# LR_meter.net
KiCad netlist of a schematic drawn in EAGLE
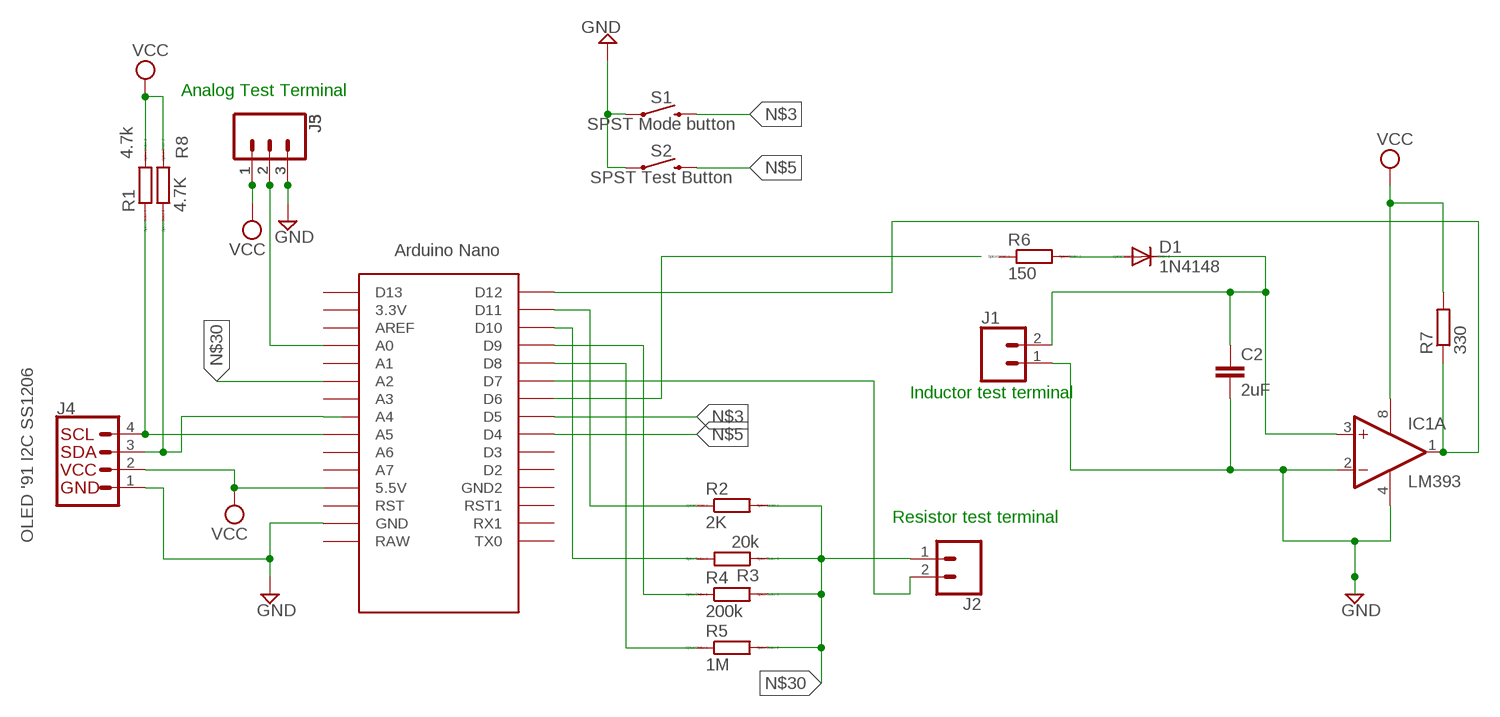
[diagram p0: schematic, sheet 1]

(export (version "E")
  (design (tool "Eeschema 10.0.6"))
  (components
    (comp (ref "C2")
      (value "2uF")
      (footprint "eagle-import:C5B2.5")
      (libsource (lib "eagle-import") (part "C5/2.5"))
    )
    (comp (ref "D1")
      (value "1N4148")
      (footprint "eagle-import:DO35-10")
      (libsource (lib "eagle-import") (part "1N4148DO35-10"))
    )
    (comp (ref "IC1")
      (value "LM393")
      (footprint "eagle-import:DIL08")
      (libsource (lib "eagle-import") (part "LM393N"))
    )
    (comp (ref "J1")
      (value "CONN_02")
      (footprint "eagle-import:1X02")
      (libsource (lib "eagle-import") (part "CONN_02"))
    )
    (comp (ref "J2")
      (value "CONN_02")
      (footprint "eagle-import:1X02")
      (libsource (lib "eagle-import") (part "CONN_02"))
    )
    (comp (ref "J3")
      (value "CONN_031X03_SMD_RA_MALE_POST_SMALLEST")
      (footprint "eagle-import:1X03_SMD_RA_MALE_POST_SMALLEST")
      (libsource (lib "eagle-import") (part "CONN_031X03_SMD_RA_MALE_POST_SMALLEST"))
    )
    (comp (ref "J4")
      (value "OLED '91 I2C SS1206")
      (footprint "eagle-import:1X04")
      (libsource (lib "eagle-import") (part "I2C_STANDARD"))
    )
    (comp (ref "J5")
      (value "CONN_031X03_SMD_RA_MALE_POST_SMALLEST")
      (footprint "eagle-import:1X03_SMD_RA_MALE_POST_SMALLEST")
      (libsource (lib "eagle-import") (part "CONN_031X03_SMD_RA_MALE_POST_SMALLEST"))
    )
    (comp (ref "R1")
      (value "4.7k")
      (footprint "eagle-import:0207_10")
      (libsource (lib "eagle-import") (part "R0207/10"))
    )
    (comp (ref "R2")
      (value "2K")
      (footprint "eagle-import:0207_10")
      (libsource (lib "eagle-import") (part "R0207/10"))
    )
    (comp (ref "R3")
      (value "20k")
      (footprint "eagle-import:0207_10")
      (libsource (lib "eagle-import") (part "R0207/10"))
    )
    (comp (ref "R4")
      (value "200k")
      (footprint "eagle-import:0207_10")
      (libsource (lib "eagle-import") (part "R0207/10"))
    )
    (comp (ref "R5")
      (value "1M")
      (footprint "eagle-import:0207_10")
      (libsource (lib "eagle-import") (part "R0207/10"))
    )
    (comp (ref "R6")
      (value "150")
      (footprint "eagle-import:0207_10")
      (libsource (lib "eagle-import") (part "R0207/10"))
    )
    (comp (ref "R7")
      (value "330")
      (footprint "eagle-import:0207_15")
      (libsource (lib "eagle-import") (part "R-EU_0207/15"))
    )
    (comp (ref "R8")
      (value "4.7K")
      (footprint "eagle-import:0207_10")
      (libsource (lib "eagle-import") (part "R0207/10"))
    )
    (comp (ref "S1")
      (value "SPST Mode button")
      (footprint "eagle-import:TACTILE_SWITCH_PTH_6.0MM_KIT")
      (libsource (lib "eagle-import") (part "MOMENTARY-SWITCH-SPST-PTH-6.0MM-KIT"))
    )
    (comp (ref "S2")
      (value "SPST Test Button")
      (footprint "eagle-import:TACTILE_SWITCH_PTH_6.0MM_KIT")
      (libsource (lib "eagle-import") (part "MOMENTARY-SWITCH-SPST-PTH-6.0MM-KIT"))
    )
    (comp (ref "U$1")
      (value "NANO")
      (footprint "eagle-import:NANO")
      (libsource (lib "eagle-import") (part "NANO"))
    )
  )
  (nets
    (net (code "1") (name "GND") (class "Default")
      (node (ref "C2") (pin "2") (pinfunction "2_2") (pintype "passive"))
      (node (ref "IC1") (pin "2") (pinfunction "-IN_2") (pintype "input"))
      (node (ref "IC1") (pin "4") (pinfunction "V-_4") (pintype "power_in"))
      (node (ref "J1") (pin "1") (pinfunction "1_1") (pintype "passive"))
      (node (ref "J3") (pin "3") (pinfunction "3_3") (pintype "passive"))
      (node (ref "J4") (pin "1") (pinfunction "1_1") (pintype "power_in"))
      (node (ref "J5") (pin "3") (pinfunction "3_3") (pintype "passive"))
      (node (ref "S1") (pin "1") (pinfunction "1_1") (pintype "passive"))
      (node (ref "S2") (pin "1") (pinfunction "1_1") (pintype "passive"))
      (node (ref "U$1") (pin "GND") (pinfunction "GND_GND") (pintype "bidirectional"))
    )
    (net (code "2") (name "N$3") (class "Default")
      (node (ref "U$1") (pin "D5") (pinfunction "D5_D5") (pintype "bidirectional"))
    )
    (net (code "3") (name "N$5") (class "Default")
      (node (ref "U$1") (pin "D4") (pinfunction "D4_D4") (pintype "bidirectional"))
    )
    (net (code "4") (name "N$30") (class "Default")
      (node (ref "J2") (pin "1") (pinfunction "1_1") (pintype "passive"))
      (node (ref "R2") (pin "2") (pinfunction "2_2") (pintype "passive"))
      (node (ref "R3") (pin "1") (pinfunction "1_1") (pintype "passive"))
      (node (ref "R4") (pin "2") (pinfunction "2_2") (pintype "passive"))
      (node (ref "R5") (pin "2") (pinfunction "2_2") (pintype "passive"))
    )
    (net (code "5") (name "Net-(D1-PadA)") (class "Default")
      (node (ref "D1") (pin "A") (pinfunction "A_A") (pintype "passive"))
      (node (ref "R6") (pin "2") (pinfunction "2_2") (pintype "passive"))
    )
    (net (code "6") (name "Net-(IC1A-+IN)") (class "Default")
      (node (ref "C2") (pin "1") (pinfunction "1_1") (pintype "passive"))
      (node (ref "D1") (pin "C") (pinfunction "C_C") (pintype "passive"))
      (node (ref "IC1") (pin "3") (pinfunction "+IN_3") (pintype "input"))
      (node (ref "J1") (pin "2") (pinfunction "2_2") (pintype "passive"))
    )
    (net (code "7") (name "Net-(IC1A-OUT)") (class "Default")
      (node (ref "IC1") (pin "1") (pinfunction "OUT_1") (pintype "output"))
      (node (ref "R7") (pin "1") (pinfunction "1_1") (pintype "passive"))
      (node (ref "U$1") (pin "D12") (pinfunction "D12_D12") (pintype "bidirectional"))
    )
    (net (code "8") (name "Net-(J2-Pad2)") (class "Default")
      (node (ref "J2") (pin "2") (pinfunction "2_2") (pintype "passive"))
      (node (ref "U$1") (pin "D7") (pinfunction "D7_D7") (pintype "bidirectional"))
    )
    (net (code "9") (name "Net-(J3-Pad2)") (class "Default")
      (node (ref "J3") (pin "2") (pinfunction "2_2") (pintype "passive"))
      (node (ref "J5") (pin "2") (pinfunction "2_2") (pintype "passive"))
      (node (ref "U$1") (pin "A0") (pinfunction "A0_A0") (pintype "bidirectional"))
    )
    (net (code "10") (name "Net-(J4-Pad3)") (class "Default")
      (node (ref "J4") (pin "3") (pinfunction "3_3") (pintype "passive"))
      (node (ref "R8") (pin "1") (pinfunction "1_1") (pintype "passive"))
      (node (ref "U$1") (pin "A4") (pinfunction "A4_A4") (pintype "bidirectional"))
    )
    (net (code "11") (name "Net-(J4-Pad4)") (class "Default")
      (node (ref "J4") (pin "4") (pinfunction "4_4") (pintype "passive"))
      (node (ref "R1") (pin "1") (pinfunction "1_1") (pintype "passive"))
      (node (ref "U$1") (pin "A5") (pinfunction "A5_A5") (pintype "bidirectional"))
    )
    (net (code "12") (name "Net-(R2-Pad1)") (class "Default")
      (node (ref "R2") (pin "1") (pinfunction "1_1") (pintype "passive"))
      (node (ref "U$1") (pin "D11") (pinfunction "D11_D11") (pintype "bidirectional"))
    )
    (net (code "13") (name "Net-(R3-Pad2)") (class "Default")
      (node (ref "R3") (pin "2") (pinfunction "2_2") (pintype "passive"))
      (node (ref "U$1") (pin "D10") (pinfunction "D10_D10") (pintype "bidirectional"))
    )
    (net (code "14") (name "Net-(R4-Pad1)") (class "Default")
      (node (ref "R4") (pin "1") (pinfunction "1_1") (pintype "passive"))
      (node (ref "U$1") (pin "D9") (pinfunction "D9_D9") (pintype "bidirectional"))
    )
    (net (code "15") (name "Net-(R5-Pad1)") (class "Default")
      (node (ref "R5") (pin "1") (pinfunction "1_1") (pintype "passive"))
      (node (ref "U$1") (pin "D8") (pinfunction "D8_D8") (pintype "bidirectional"))
    )
    (net (code "16") (name "VCC") (class "Default")
      (node (ref "IC1") (pin "8") (pinfunction "V+_8") (pintype "power_in"))
      (node (ref "J3") (pin "1") (pinfunction "1_1") (pintype "passive"))
      (node (ref "J4") (pin "2") (pinfunction "2_2") (pintype "power_in"))
      (node (ref "J5") (pin "1") (pinfunction "1_1") (pintype "passive"))
      (node (ref "R1") (pin "2") (pinfunction "2_2") (pintype "passive"))
      (node (ref "R7") (pin "2") (pinfunction "2_2") (pintype "passive"))
      (node (ref "R8") (pin "2") (pinfunction "2_2") (pintype "passive"))
      (node (ref "U$1") (pin "5V") (pinfunction "5.5V_5V") (pintype "bidirectional"))
    )
    (net (code "17") (name "unconnected-(R6-Pad1)") (class "Default")
      (node (ref "R6") (pin "1") (pinfunction "1_1") (pintype "passive"))
    )
    (net (code "18") (name "unconnected-(S1-2-Pad3)") (class "Default")
      (node (ref "S1") (pin "3") (pinfunction "2_3") (pintype "passive"))
    )
    (net (code "19") (name "unconnected-(S2-2-Pad3)") (class "Default")
      (node (ref "S2") (pin "3") (pinfunction "2_3") (pintype "passive"))
    )
    (net (code "20") (name "unconnected-(U$1-GND2-PadGND1)") (class "Default")
      (node (ref "U$1") (pin "GND1") (pinfunction "GND2_GND1") (pintype "bidirectional"))
    )
    (net (code "21") (name "unconnected-(U$1-Pad3.3V)") (class "Default")
      (node (ref "U$1") (pin "3.3V") (pinfunction "3.3V_3.3V") (pintype "bidirectional"))
    )
    (net (code "22") (name "unconnected-(U$1-PadA1)") (class "Default")
      (node (ref "U$1") (pin "A1") (pinfunction "A1_A1") (pintype "bidirectional"))
    )
    (net (code "23") (name "unconnected-(U$1-PadA2)") (class "Default")
      (node (ref "U$1") (pin "A2") (pinfunction "A2_A2") (pintype "bidirectional"))
    )
    (net (code "24") (name "unconnected-(U$1-PadA3)") (class "Default")
      (node (ref "U$1") (pin "A3") (pinfunction "A3_A3") (pintype "bidirectional"))
    )
    (net (code "25") (name "unconnected-(U$1-PadA6)") (class "Default")
      (node (ref "U$1") (pin "A6") (pinfunction "A6_A6") (pintype "bidirectional"))
    )
    (net (code "26") (name "unconnected-(U$1-PadA7)") (class "Default")
      (node (ref "U$1") (pin "A7") (pinfunction "A7_A7") (pintype "bidirectional"))
    )
    (net (code "27") (name "unconnected-(U$1-PadAREF)") (class "Default")
      (node (ref "U$1") (pin "AREF") (pinfunction "AREF_AREF") (pintype "bidirectional"))
    )
    (net (code "28") (name "unconnected-(U$1-PadD2)") (class "Default")
      (node (ref "U$1") (pin "D2") (pinfunction "D2_D2") (pintype "bidirectional"))
    )
    (net (code "29") (name "unconnected-(U$1-PadD3)") (class "Default")
      (node (ref "U$1") (pin "D3") (pinfunction "D3_D3") (pintype "bidirectional"))
    )
    (net (code "30") (name "unconnected-(U$1-PadD6)") (class "Default")
      (node (ref "U$1") (pin "D6") (pinfunction "D6_D6") (pintype "bidirectional"))
    )
    (net (code "31") (name "unconnected-(U$1-PadD13)") (class "Default")
      (node (ref "U$1") (pin "D13") (pinfunction "D13_D13") (pintype "bidirectional"))
    )
    (net (code "32") (name "unconnected-(U$1-PadICSP1)") (class "Default")
      (node (ref "U$1") (pin "ICSP1") (pinfunction "ICSP1_ICSP1") (pintype "bidirectional"))
    )
    (net (code "33") (name "unconnected-(U$1-PadICSP2)") (class "Default")
      (node (ref "U$1") (pin "ICSP2") (pinfunction "ICSP2_ICSP2") (pintype "bidirectional"))
    )
    (net (code "34") (name "unconnected-(U$1-PadICSP3)") (class "Default")
      (node (ref "U$1") (pin "ICSP3") (pinfunction "ICSP3_ICSP3") (pintype "bidirectional"))
    )
    (net (code "35") (name "unconnected-(U$1-PadICSP4)") (class "Default")
      (node (ref "U$1") (pin "ICSP4") (pinfunction "ICSP4_ICSP4") (pintype "bidirectional"))
    )
    (net (code "36") (name "unconnected-(U$1-PadICSP5)") (class "Default")
      (node (ref "U$1") (pin "ICSP5") (pinfunction "ICSP5_ICSP5") (pintype "bidirectional"))
    )
    (net (code "37") (name "unconnected-(U$1-PadICSP6)") (class "Default")
      (node (ref "U$1") (pin "ICSP6") (pinfunction "ICSP6_ICSP6") (pintype "bidirectional"))
    )
    (net (code "38") (name "unconnected-(U$1-PadRAW)") (class "Default")
      (node (ref "U$1") (pin "RAW") (pinfunction "RAW_RAW") (pintype "bidirectional"))
    )
    (net (code "39") (name "unconnected-(U$1-PadRST)") (class "Default")
      (node (ref "U$1") (pin "RST") (pinfunction "RST_RST") (pintype "bidirectional"))
    )
    (net (code "40") (name "unconnected-(U$1-PadRST1)") (class "Default")
      (node (ref "U$1") (pin "RST1") (pinfunction "RST1_RST1") (pintype "bidirectional"))
    )
    (net (code "41") (name "unconnected-(U$1-PadRX1)") (class "Default")
      (node (ref "U$1") (pin "RX1") (pinfunction "RX1_RX1") (pintype "bidirectional"))
    )
    (net (code "42") (name "unconnected-(U$1-PadTX0)") (class "Default")
      (node (ref "U$1") (pin "TX0") (pinfunction "TX0_TX0") (pintype "bidirectional"))
    )
  )
)
